# US_EPS_SP.net
KiCad netlist of a schematic drawn in Altium Designer
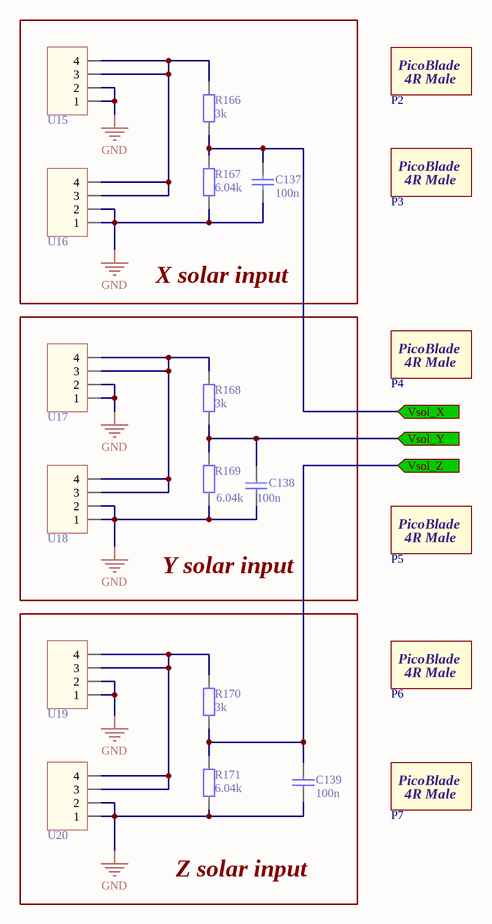
[diagram p0: US_EPS_SP.SchDoc]

(export (version "E")
  (design (tool "Eeschema 10.0.6"))
  (components
    (comp (ref "C137")
      (value "100n")
      (footprint "C0603_IPC_HD")
      (description "CAP CER 0.1UF 16V X7R 0603")
      (fields
        (field (name "MANUFACTURER") "Samsung Electro-Mechanics")
        (field (name "MANUFACTURER PART NUMBER") "CL10B104KO8NNNC")
      )
      (libsource (lib "alfasat_lib") (part "CL10B104KO8NNNC"))
    )
    (comp (ref "C138")
      (value "100n")
      (footprint "C0603_IPC_HD")
      (description "CAP CER 0.1UF 16V X7R 0603")
      (fields
        (field (name "MANUFACTURER") "Samsung Electro-Mechanics")
        (field (name "MANUFACTURER PART NUMBER") "CL10B104KO8NNNC")
      )
      (libsource (lib "alfasat_lib") (part "CL10B104KO8NNNC"))
    )
    (comp (ref "C139")
      (value "100n")
      (footprint "C0603_IPC_HD")
      (description "CAP CER 0.1UF 16V X7R 0603")
      (fields
        (field (name "MANUFACTURER") "Samsung Electro-Mechanics")
        (field (name "MANUFACTURER PART NUMBER") "CL10B104KO8NNNC")
      )
      (libsource (lib "alfasat_lib") (part "CL10B104KO8NNNC"))
    )
    (comp (ref "P2")
      (value "PicoBlade_4R_MALE")
      (description "MALE Connector Header Surface Mount 4 position 0.049\" (1.25mm)")
      (fields (field (name "MANUFACTURER") "China"))
      (libsource (lib "alfasat_lib_eps") (part "PicoBlade_4R_M"))
    )
    (comp (ref "P3")
      (value "PicoBlade_4R_MALE")
      (description "MALE Connector Header Surface Mount 4 position 0.049\" (1.25mm)")
      (fields (field (name "MANUFACTURER") "China"))
      (libsource (lib "alfasat_lib_eps") (part "PicoBlade_4R_M"))
    )
    (comp (ref "P4")
      (value "PicoBlade_4R_MALE")
      (description "MALE Connector Header Surface Mount 4 position 0.049\" (1.25mm)")
      (fields (field (name "MANUFACTURER") "China"))
      (libsource (lib "alfasat_lib_eps") (part "PicoBlade_4R_M"))
    )
    (comp (ref "P5")
      (value "PicoBlade_4R_MALE")
      (description "MALE Connector Header Surface Mount 4 position 0.049\" (1.25mm)")
      (fields (field (name "MANUFACTURER") "China"))
      (libsource (lib "alfasat_lib_eps") (part "PicoBlade_4R_M"))
    )
    (comp (ref "P6")
      (value "PicoBlade_4R_MALE")
      (description "MALE Connector Header Surface Mount 4 position 0.049\" (1.25mm)")
      (fields (field (name "MANUFACTURER") "China"))
      (libsource (lib "alfasat_lib_eps") (part "PicoBlade_4R_M"))
    )
    (comp (ref "P7")
      (value "PicoBlade_4R_MALE")
      (description "MALE Connector Header Surface Mount 4 position 0.049\" (1.25mm)")
      (fields (field (name "MANUFACTURER") "China"))
      (libsource (lib "alfasat_lib_eps") (part "PicoBlade_4R_M"))
    )
    (comp (ref "R166")
      (value "3k")
      (footprint "C0603_IPC_HD")
      (description "RES SMD 3K OHM 5% 1/10W 0603")
      (fields
        (field (name "MANUFACTURER") "Bourns Inc.")
        (field (name "MANUFACTURER PART NUMBER") "CR0603-JW-302ELF")
      )
      (libsource (lib "alfasat_lib_eps") (part "CR0603-JW-3k"))
    )
    (comp (ref "R167")
      (value "6.04k")
      (footprint "C0603_IPC_HD")
      (description "RES 6.04K OHM 1% 1/10W 0603")
      (fields
        (field (name "MANUFACTURER") "Stackpole Electronics Inc")
        (field (name "MANUFACTURER PART NUMBER") "RMCF0603FT6K04")
      )
      (libsource (lib "alfasat_lib_eps") (part "CR0603-JW-6.04K"))
    )
    (comp (ref "R168")
      (value "3k")
      (footprint "C0603_IPC_HD")
      (description "RES SMD 3K OHM 5% 1/10W 0603")
      (fields
        (field (name "MANUFACTURER") "Bourns Inc.")
        (field (name "MANUFACTURER PART NUMBER") "CR0603-JW-302ELF")
      )
      (libsource (lib "alfasat_lib_eps") (part "CR0603-JW-3k"))
    )
    (comp (ref "R169")
      (value "6.04k")
      (footprint "C0603_IPC_HD")
      (description "RES 6.04K OHM 1% 1/10W 0603")
      (fields
        (field (name "MANUFACTURER") "Stackpole Electronics Inc")
        (field (name "MANUFACTURER PART NUMBER") "RMCF0603FT6K04")
      )
      (libsource (lib "alfasat_lib_eps") (part "CR0603-JW-6.04K"))
    )
    (comp (ref "R170")
      (value "3k")
      (footprint "C0603_IPC_HD")
      (description "RES SMD 3K OHM 5% 1/10W 0603")
      (fields
        (field (name "MANUFACTURER") "Bourns Inc.")
        (field (name "MANUFACTURER PART NUMBER") "CR0603-JW-302ELF")
      )
      (libsource (lib "alfasat_lib_eps") (part "CR0603-JW-3k"))
    )
    (comp (ref "R171")
      (value "6.04k")
      (footprint "C0603_IPC_HD")
      (description "RES 6.04K OHM 1% 1/10W 0603")
      (fields
        (field (name "MANUFACTURER") "Stackpole Electronics Inc")
        (field (name "MANUFACTURER PART NUMBER") "RMCF0603FT6K04")
      )
      (libsource (lib "alfasat_lib_eps") (part "CR0603-JW-6.04K"))
    )
    (comp (ref "U15")
      (value "PicoBlade_4R")
      (footprint "PB_53261-0471_Right")
      (description "Connector Header Surface Mount 4 position 0.049\" (1.25mm)")
      (fields (field (name "MANUFACTURER") "China"))
      (libsource (lib "alfasat_parts_lib") (part "PicoBlade_4R"))
    )
    (comp (ref "U16")
      (value "PicoBlade_4R")
      (footprint "PB_53261-0471_Right")
      (description "Connector Header Surface Mount 4 position 0.049\" (1.25mm)")
      (fields (field (name "MANUFACTURER") "China"))
      (libsource (lib "alfasat_parts_lib") (part "PicoBlade_4R"))
    )
    (comp (ref "U17")
      (value "PicoBlade_4R")
      (footprint "PB_53261-0471_Right")
      (description "Connector Header Surface Mount 4 position 0.049\" (1.25mm)")
      (fields (field (name "MANUFACTURER") "China"))
      (libsource (lib "alfasat_parts_lib") (part "PicoBlade_4R"))
    )
    (comp (ref "U18")
      (value "PicoBlade_4R")
      (footprint "PB_53261-0471_Right")
      (description "Connector Header Surface Mount 4 position 0.049\" (1.25mm)")
      (fields (field (name "MANUFACTURER") "China"))
      (libsource (lib "alfasat_parts_lib") (part "PicoBlade_4R"))
    )
    (comp (ref "U19")
      (value "PicoBlade_4R")
      (footprint "PB_53261-0471_Right")
      (description "Connector Header Surface Mount 4 position 0.049\" (1.25mm)")
      (fields (field (name "MANUFACTURER") "China"))
      (libsource (lib "alfasat_parts_lib") (part "PicoBlade_4R"))
    )
    (comp (ref "U20")
      (value "PicoBlade_4R")
      (footprint "PB_53261-0471_Right")
      (description "Connector Header Surface Mount 4 position 0.049\" (1.25mm)")
      (fields (field (name "MANUFACTURER") "China"))
      (libsource (lib "alfasat_parts_lib") (part "PicoBlade_4R"))
    )
  )
  (nets
    (net (code "1") (name "/Vsol_X") (class "Default")
      (node (ref "C137") (pin "2") (pinfunction "2_2") (pintype "passive"))
      (node (ref "R166") (pin "1") (pinfunction "1_1") (pintype "passive"))
      (node (ref "R167") (pin "2") (pinfunction "2_2") (pintype "passive"))
    )
    (net (code "2") (name "/Vsol_Y") (class "Default")
      (node (ref "C138") (pin "2") (pinfunction "2_2") (pintype "passive"))
      (node (ref "R168") (pin "1") (pinfunction "1_1") (pintype "passive"))
      (node (ref "R169") (pin "2") (pinfunction "2_2") (pintype "passive"))
    )
    (net (code "3") (name "/Vsol_Z") (class "Default")
      (node (ref "C139") (pin "2") (pinfunction "2_2") (pintype "passive"))
      (node (ref "R170") (pin "1") (pinfunction "1_1") (pintype "passive"))
      (node (ref "R171") (pin "2") (pinfunction "2_2") (pintype "passive"))
    )
    (net (code "4") (name "GND") (class "Default")
      (node (ref "C137") (pin "1") (pinfunction "1_1") (pintype "passive"))
      (node (ref "C138") (pin "1") (pinfunction "1_1") (pintype "passive"))
      (node (ref "C139") (pin "1") (pinfunction "1_1") (pintype "passive"))
      (node (ref "R167") (pin "1") (pinfunction "1_1") (pintype "passive"))
      (node (ref "R169") (pin "1") (pinfunction "1_1") (pintype "passive"))
      (node (ref "R171") (pin "1") (pinfunction "1_1") (pintype "passive"))
      (node (ref "U15") (pin "1") (pinfunction "1_1") (pintype "passive"))
      (node (ref "U15") (pin "2") (pinfunction "2_2") (pintype "passive"))
      (node (ref "U16") (pin "1") (pinfunction "1_1") (pintype "passive"))
      (node (ref "U16") (pin "2") (pinfunction "2_2") (pintype "passive"))
      (node (ref "U17") (pin "1") (pinfunction "1_1") (pintype "passive"))
      (node (ref "U17") (pin "2") (pinfunction "2_2") (pintype "passive"))
      (node (ref "U18") (pin "1") (pinfunction "1_1") (pintype "passive"))
      (node (ref "U18") (pin "2") (pinfunction "2_2") (pintype "passive"))
      (node (ref "U19") (pin "1") (pinfunction "1_1") (pintype "passive"))
      (node (ref "U19") (pin "2") (pinfunction "2_2") (pintype "passive"))
      (node (ref "U20") (pin "1") (pinfunction "1_1") (pintype "passive"))
      (node (ref "U20") (pin "2") (pinfunction "2_2") (pintype "passive"))
    )
    (net (code "5") (name "Net-(R166-Pad2)") (class "Default")
      (node (ref "R166") (pin "2") (pinfunction "2_2") (pintype "passive"))
      (node (ref "U15") (pin "3") (pinfunction "3_3") (pintype "passive"))
      (node (ref "U15") (pin "4") (pinfunction "4_4") (pintype "passive"))
      (node (ref "U16") (pin "3") (pinfunction "3_3") (pintype "passive"))
      (node (ref "U16") (pin "4") (pinfunction "4_4") (pintype "passive"))
    )
    (net (code "6") (name "Net-(R168-Pad2)") (class "Default")
      (node (ref "R168") (pin "2") (pinfunction "2_2") (pintype "passive"))
      (node (ref "U17") (pin "3") (pinfunction "3_3") (pintype "passive"))
      (node (ref "U17") (pin "4") (pinfunction "4_4") (pintype "passive"))
      (node (ref "U18") (pin "3") (pinfunction "3_3") (pintype "passive"))
      (node (ref "U18") (pin "4") (pinfunction "4_4") (pintype "passive"))
    )
    (net (code "7") (name "Net-(R170-Pad2)") (class "Default")
      (node (ref "R170") (pin "2") (pinfunction "2_2") (pintype "passive"))
      (node (ref "U19") (pin "3") (pinfunction "3_3") (pintype "passive"))
      (node (ref "U19") (pin "4") (pinfunction "4_4") (pintype "passive"))
      (node (ref "U20") (pin "3") (pinfunction "3_3") (pintype "passive"))
      (node (ref "U20") (pin "4") (pinfunction "4_4") (pintype "passive"))
    )
  )
)
